# IV9.net
KiCad netlist of a schematic drawn in EAGLE
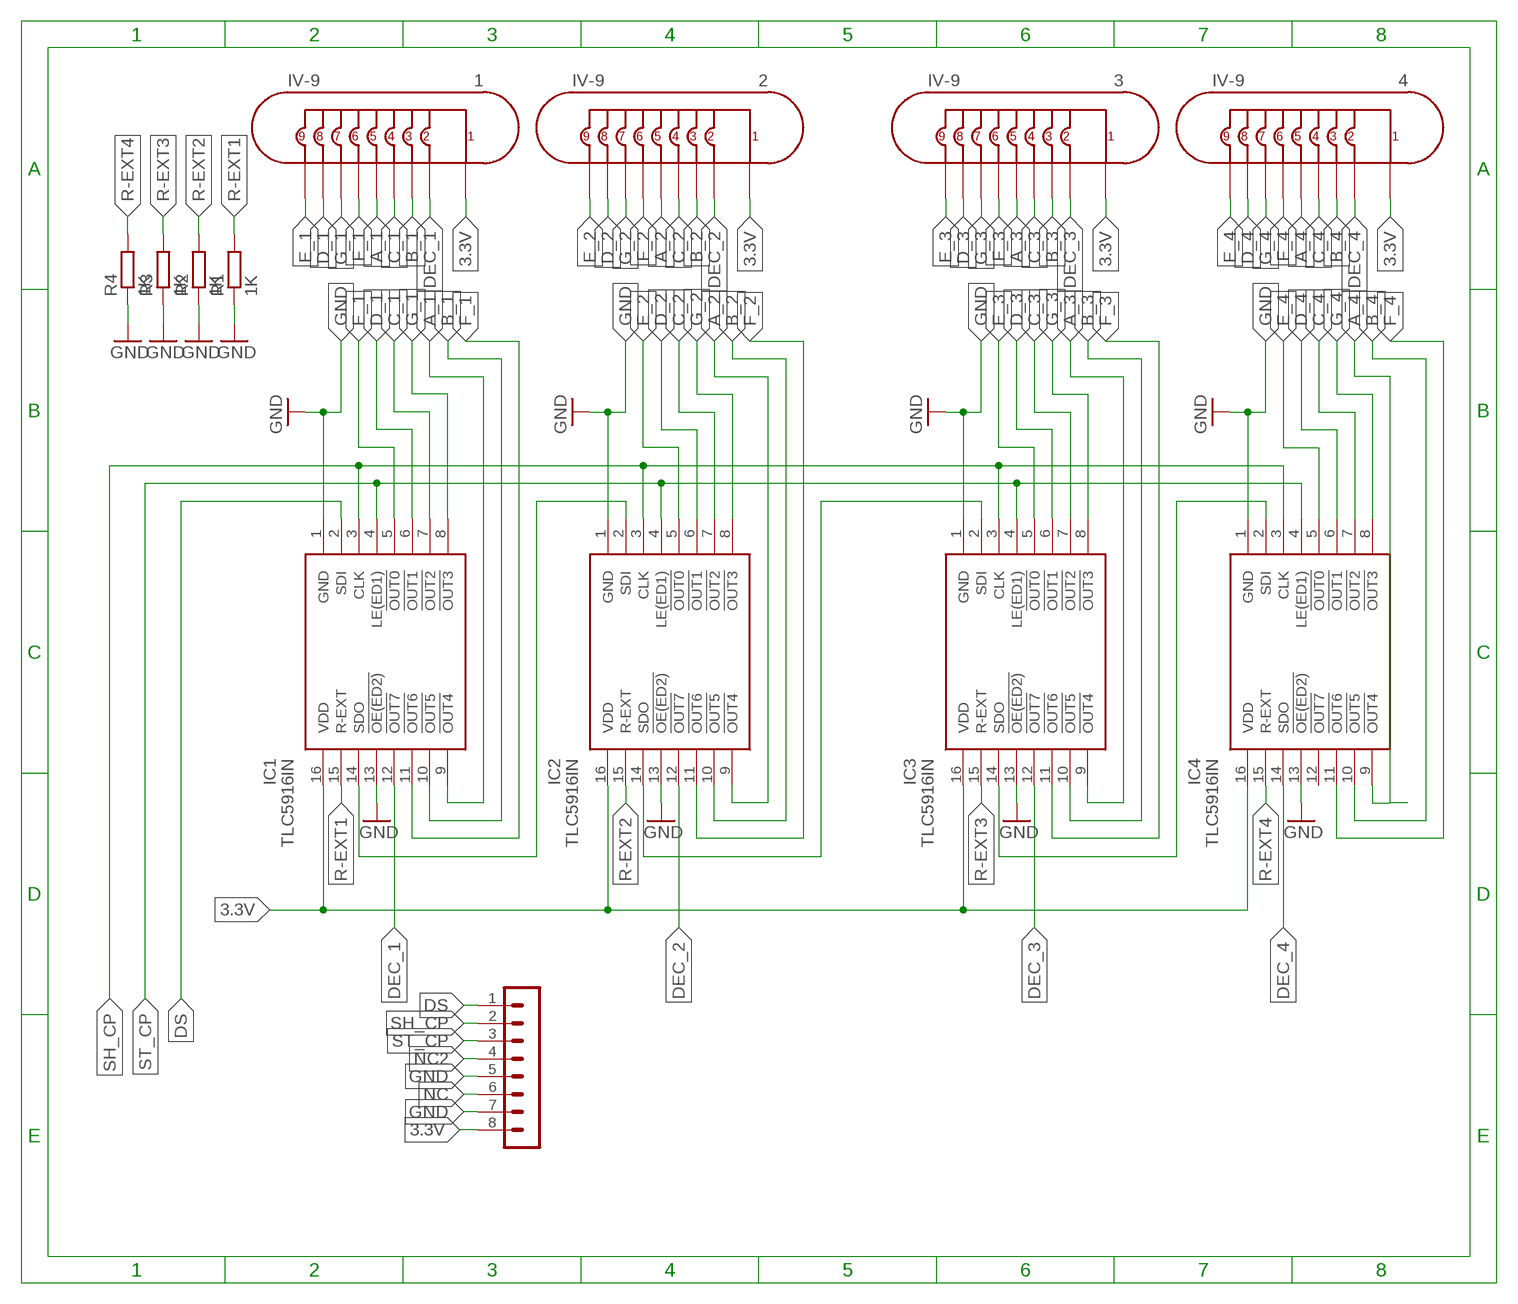
[diagram p0: schematic, sheet 1]

(export (version "E")
  (design (tool "Eeschema 10.0.6"))
  (components
    (comp (ref "1")
      (value "IV-9")
      (footprint "eagle-import:IV-9")
      (libsource (lib "eagle-import") (part "IV-9"))
    )
    (comp (ref "2")
      (value "IV-9")
      (footprint "eagle-import:IV-9")
      (libsource (lib "eagle-import") (part "IV-9"))
    )
    (comp (ref "3")
      (value "IV-9")
      (footprint "eagle-import:IV-9")
      (libsource (lib "eagle-import") (part "IV-9"))
    )
    (comp (ref "4")
      (value "IV-9")
      (footprint "eagle-import:IV-9")
      (libsource (lib "eagle-import") (part "IV-9"))
    )
    (comp (ref "IC1")
      (value "TLC5916IN")
      (footprint "eagle-import:DIP794W53P254L1930H508Q16N")
      (fields (field (name "MOUSER_PART_NUMBER") "595-TLC5916IN"))
      (libsource (lib "eagle-import") (part "TLC5916IN"))
    )
    (comp (ref "IC2")
      (value "TLC5916IN")
      (footprint "eagle-import:DIP794W53P254L1930H508Q16N")
      (fields (field (name "MOUSER_PART_NUMBER") "595-TLC5916IN"))
      (libsource (lib "eagle-import") (part "TLC5916IN"))
    )
    (comp (ref "IC3")
      (value "TLC5916IN")
      (footprint "eagle-import:DIP794W53P254L1930H508Q16N")
      (fields (field (name "MOUSER_PART_NUMBER") "595-TLC5916IN"))
      (libsource (lib "eagle-import") (part "TLC5916IN"))
    )
    (comp (ref "IC4")
      (value "TLC5916IN")
      (footprint "eagle-import:DIP794W53P254L1930H508Q16N")
      (fields (field (name "MOUSER_PART_NUMBER") "595-TLC5916IN"))
      (libsource (lib "eagle-import") (part "TLC5916IN"))
    )
    (comp (ref "R1")
      (value "1K")
      (footprint "eagle-import:R1206")
      (libsource (lib "eagle-import") (part "R-EU_R1206"))
    )
    (comp (ref "R2")
      (value "1K")
      (footprint "eagle-import:R1206")
      (libsource (lib "eagle-import") (part "R-EU_R1206"))
    )
    (comp (ref "R3")
      (value "1K")
      (footprint "eagle-import:R1206")
      (libsource (lib "eagle-import") (part "R-EU_R1206"))
    )
    (comp (ref "R4")
      (value "1K")
      (footprint "eagle-import:R1206")
      (libsource (lib "eagle-import") (part "R-EU_R1206"))
    )
    (comp (ref "SV2")
      (value "PINHEADER-1X8")
      (footprint "eagle-import:MA08-1")
      (libsource (lib "eagle-import") (part "PINHEADER-1X8"))
    )
  )
  (nets
    (net (code "1") (name "3.3V") (class "Default")
      (node (ref "1") (pin "1") (pinfunction "1_1") (pintype "bidirectional"))
      (node (ref "2") (pin "1") (pinfunction "1_1") (pintype "bidirectional"))
      (node (ref "3") (pin "1") (pinfunction "1_1") (pintype "bidirectional"))
      (node (ref "4") (pin "1") (pinfunction "1_1") (pintype "bidirectional"))
      (node (ref "IC1") (pin "16") (pinfunction "VDD_16") (pintype "bidirectional"))
      (node (ref "IC2") (pin "16") (pinfunction "VDD_16") (pintype "bidirectional"))
      (node (ref "IC3") (pin "16") (pinfunction "VDD_16") (pintype "bidirectional"))
      (node (ref "IC4") (pin "16") (pinfunction "VDD_16") (pintype "bidirectional"))
      (node (ref "SV2") (pin "8") (pinfunction "8_8") (pintype "passive"))
    )
    (net (code "2") (name "A_1") (class "Default")
      (node (ref "1") (pin "5") (pinfunction "5_5") (pintype "bidirectional"))
      (node (ref "IC1") (pin "9") (pinfunction "~{OUT4}_9") (pintype "bidirectional"))
    )
    (net (code "3") (name "A_2") (class "Default")
      (node (ref "2") (pin "5") (pinfunction "5_5") (pintype "bidirectional"))
      (node (ref "IC2") (pin "9") (pinfunction "~{OUT4}_9") (pintype "bidirectional"))
    )
    (net (code "4") (name "A_3") (class "Default")
      (node (ref "3") (pin "5") (pinfunction "5_5") (pintype "bidirectional"))
      (node (ref "IC3") (pin "9") (pinfunction "~{OUT4}_9") (pintype "bidirectional"))
    )
    (net (code "5") (name "A_4") (class "Default")
      (node (ref "4") (pin "5") (pinfunction "5_5") (pintype "bidirectional"))
      (node (ref "IC4") (pin "9") (pinfunction "~{OUT4}_9") (pintype "bidirectional"))
    )
    (net (code "6") (name "B_1") (class "Default")
      (node (ref "1") (pin "3") (pinfunction "3_3") (pintype "bidirectional"))
      (node (ref "IC1") (pin "10") (pinfunction "~{OUT5}_10") (pintype "bidirectional"))
    )
    (net (code "7") (name "B_2") (class "Default")
      (node (ref "2") (pin "3") (pinfunction "3_3") (pintype "bidirectional"))
      (node (ref "IC2") (pin "10") (pinfunction "~{OUT5}_10") (pintype "bidirectional"))
    )
    (net (code "8") (name "B_3") (class "Default")
      (node (ref "3") (pin "3") (pinfunction "3_3") (pintype "bidirectional"))
      (node (ref "IC3") (pin "10") (pinfunction "~{OUT5}_10") (pintype "bidirectional"))
    )
    (net (code "9") (name "B_4") (class "Default")
      (node (ref "4") (pin "3") (pinfunction "3_3") (pintype "bidirectional"))
      (node (ref "IC4") (pin "10") (pinfunction "~{OUT5}_10") (pintype "bidirectional"))
    )
    (net (code "10") (name "C_1") (class "Default")
      (node (ref "1") (pin "4") (pinfunction "4_4") (pintype "bidirectional"))
      (node (ref "IC1") (pin "7") (pinfunction "~{OUT2}_7") (pintype "bidirectional"))
    )
    (net (code "11") (name "C_2") (class "Default")
      (node (ref "2") (pin "4") (pinfunction "4_4") (pintype "bidirectional"))
      (node (ref "IC2") (pin "7") (pinfunction "~{OUT2}_7") (pintype "bidirectional"))
    )
    (net (code "12") (name "C_3") (class "Default")
      (node (ref "3") (pin "4") (pinfunction "4_4") (pintype "bidirectional"))
      (node (ref "IC3") (pin "7") (pinfunction "~{OUT2}_7") (pintype "bidirectional"))
    )
    (net (code "13") (name "C_4") (class "Default")
      (node (ref "4") (pin "4") (pinfunction "4_4") (pintype "bidirectional"))
      (node (ref "IC4") (pin "7") (pinfunction "~{OUT2}_7") (pintype "bidirectional"))
    )
    (net (code "14") (name "DEC_1") (class "Default")
      (node (ref "1") (pin "2") (pinfunction "2_2") (pintype "bidirectional"))
      (node (ref "IC1") (pin "12") (pinfunction "~{OUT7}_12") (pintype "bidirectional"))
    )
    (net (code "15") (name "DEC_2") (class "Default")
      (node (ref "2") (pin "2") (pinfunction "2_2") (pintype "bidirectional"))
      (node (ref "IC2") (pin "12") (pinfunction "~{OUT7}_12") (pintype "bidirectional"))
    )
    (net (code "16") (name "DEC_3") (class "Default")
      (node (ref "3") (pin "2") (pinfunction "2_2") (pintype "bidirectional"))
      (node (ref "IC3") (pin "12") (pinfunction "~{OUT7}_12") (pintype "bidirectional"))
    )
    (net (code "17") (name "DEC_4") (class "Default")
      (node (ref "4") (pin "2") (pinfunction "2_2") (pintype "bidirectional"))
      (node (ref "IC4") (pin "14") (pinfunction "SDO_14") (pintype "bidirectional"))
    )
    (net (code "18") (name "DS") (class "Default")
      (node (ref "IC1") (pin "2") (pinfunction "SDI_2") (pintype "bidirectional"))
      (node (ref "SV2") (pin "1") (pinfunction "1_1") (pintype "passive"))
    )
    (net (code "19") (name "D_1") (class "Default")
      (node (ref "1") (pin "8") (pinfunction "8_8") (pintype "bidirectional"))
      (node (ref "IC1") (pin "6") (pinfunction "~{OUT1}_6") (pintype "bidirectional"))
    )
    (net (code "20") (name "D_2") (class "Default")
      (node (ref "2") (pin "8") (pinfunction "8_8") (pintype "bidirectional"))
      (node (ref "IC2") (pin "6") (pinfunction "~{OUT1}_6") (pintype "bidirectional"))
    )
    (net (code "21") (name "D_3") (class "Default")
      (node (ref "3") (pin "8") (pinfunction "8_8") (pintype "bidirectional"))
      (node (ref "IC3") (pin "6") (pinfunction "~{OUT1}_6") (pintype "bidirectional"))
    )
    (net (code "22") (name "D_4") (class "Default")
      (node (ref "4") (pin "8") (pinfunction "8_8") (pintype "bidirectional"))
      (node (ref "IC4") (pin "6") (pinfunction "~{OUT1}_6") (pintype "bidirectional"))
    )
    (net (code "23") (name "E_1") (class "Default")
      (node (ref "1") (pin "9") (pinfunction "9_9") (pintype "bidirectional"))
      (node (ref "IC1") (pin "5") (pinfunction "~{OUT0}_5") (pintype "bidirectional"))
    )
    (net (code "24") (name "E_2") (class "Default")
      (node (ref "2") (pin "9") (pinfunction "9_9") (pintype "bidirectional"))
      (node (ref "IC2") (pin "5") (pinfunction "~{OUT0}_5") (pintype "bidirectional"))
    )
    (net (code "25") (name "E_3") (class "Default")
      (node (ref "3") (pin "9") (pinfunction "9_9") (pintype "bidirectional"))
      (node (ref "IC3") (pin "5") (pinfunction "~{OUT0}_5") (pintype "bidirectional"))
    )
    (net (code "26") (name "E_4") (class "Default")
      (node (ref "4") (pin "9") (pinfunction "9_9") (pintype "bidirectional"))
      (node (ref "IC4") (pin "5") (pinfunction "~{OUT0}_5") (pintype "bidirectional"))
    )
    (net (code "27") (name "F_1") (class "Default")
      (node (ref "1") (pin "6") (pinfunction "6_6") (pintype "bidirectional"))
      (node (ref "IC1") (pin "11") (pinfunction "~{OUT6}_11") (pintype "bidirectional"))
    )
    (net (code "28") (name "F_2") (class "Default")
      (node (ref "2") (pin "6") (pinfunction "6_6") (pintype "bidirectional"))
      (node (ref "IC2") (pin "11") (pinfunction "~{OUT6}_11") (pintype "bidirectional"))
    )
    (net (code "29") (name "F_3") (class "Default")
      (node (ref "3") (pin "6") (pinfunction "6_6") (pintype "bidirectional"))
      (node (ref "IC3") (pin "11") (pinfunction "~{OUT6}_11") (pintype "bidirectional"))
    )
    (net (code "30") (name "F_4") (class "Default")
      (node (ref "4") (pin "6") (pinfunction "6_6") (pintype "bidirectional"))
      (node (ref "IC4") (pin "11") (pinfunction "~{OUT6}_11") (pintype "bidirectional"))
    )
    (net (code "31") (name "GND") (class "Default")
      (node (ref "IC1") (pin "1") (pinfunction "GND_1") (pintype "bidirectional"))
      (node (ref "IC1") (pin "13") (pinfunction "~{OE(ED2})_13") (pintype "bidirectional"))
      (node (ref "IC2") (pin "1") (pinfunction "GND_1") (pintype "bidirectional"))
      (node (ref "IC2") (pin "13") (pinfunction "~{OE(ED2})_13") (pintype "bidirectional"))
      (node (ref "IC3") (pin "1") (pinfunction "GND_1") (pintype "bidirectional"))
      (node (ref "IC3") (pin "13") (pinfunction "~{OE(ED2})_13") (pintype "bidirectional"))
      (node (ref "IC4") (pin "1") (pinfunction "GND_1") (pintype "bidirectional"))
      (node (ref "IC4") (pin "13") (pinfunction "~{OE(ED2})_13") (pintype "bidirectional"))
      (node (ref "R1") (pin "1") (pinfunction "1_1") (pintype "passive"))
      (node (ref "R2") (pin "1") (pinfunction "1_1") (pintype "passive"))
      (node (ref "R3") (pin "1") (pinfunction "1_1") (pintype "passive"))
      (node (ref "R4") (pin "1") (pinfunction "1_1") (pintype "passive"))
      (node (ref "SV2") (pin "5") (pinfunction "5_5") (pintype "passive"))
      (node (ref "SV2") (pin "7") (pinfunction "7_7") (pintype "passive"))
    )
    (net (code "32") (name "G_1") (class "Default")
      (node (ref "1") (pin "7") (pinfunction "7_7") (pintype "bidirectional"))
      (node (ref "IC1") (pin "8") (pinfunction "~{OUT3}_8") (pintype "bidirectional"))
    )
    (net (code "33") (name "G_2") (class "Default")
      (node (ref "2") (pin "7") (pinfunction "7_7") (pintype "bidirectional"))
      (node (ref "IC2") (pin "8") (pinfunction "~{OUT3}_8") (pintype "bidirectional"))
    )
    (net (code "34") (name "G_3") (class "Default")
      (node (ref "3") (pin "7") (pinfunction "7_7") (pintype "bidirectional"))
      (node (ref "IC3") (pin "8") (pinfunction "~{OUT3}_8") (pintype "bidirectional"))
    )
    (net (code "35") (name "G_4") (class "Default")
      (node (ref "4") (pin "7") (pinfunction "7_7") (pintype "bidirectional"))
      (node (ref "IC4") (pin "8") (pinfunction "~{OUT3}_8") (pintype "bidirectional"))
    )
    (net (code "36") (name "NC") (class "Default")
      (node (ref "SV2") (pin "6") (pinfunction "6_6") (pintype "passive"))
    )
    (net (code "37") (name "NC2") (class "Default")
      (node (ref "SV2") (pin "4") (pinfunction "4_4") (pintype "passive"))
    )
    (net (code "38") (name "Net-(IC1-SDO)") (class "Default")
      (node (ref "IC1") (pin "14") (pinfunction "SDO_14") (pintype "bidirectional"))
      (node (ref "IC2") (pin "2") (pinfunction "SDI_2") (pintype "bidirectional"))
    )
    (net (code "39") (name "Net-(IC2-SDO)") (class "Default")
      (node (ref "IC2") (pin "14") (pinfunction "SDO_14") (pintype "bidirectional"))
      (node (ref "IC3") (pin "2") (pinfunction "SDI_2") (pintype "bidirectional"))
    )
    (net (code "40") (name "Net-(IC3-SDO)") (class "Default")
      (node (ref "IC3") (pin "14") (pinfunction "SDO_14") (pintype "bidirectional"))
      (node (ref "IC4") (pin "2") (pinfunction "SDI_2") (pintype "bidirectional"))
    )
    (net (code "41") (name "R-EXT1") (class "Default")
      (node (ref "IC1") (pin "15") (pinfunction "R-EXT_15") (pintype "bidirectional"))
      (node (ref "R1") (pin "2") (pinfunction "2_2") (pintype "passive"))
    )
    (net (code "42") (name "R-EXT2") (class "Default")
      (node (ref "IC2") (pin "15") (pinfunction "R-EXT_15") (pintype "bidirectional"))
      (node (ref "R2") (pin "2") (pinfunction "2_2") (pintype "passive"))
    )
    (net (code "43") (name "R-EXT3") (class "Default")
      (node (ref "IC3") (pin "15") (pinfunction "R-EXT_15") (pintype "bidirectional"))
      (node (ref "R3") (pin "2") (pinfunction "2_2") (pintype "passive"))
    )
    (net (code "44") (name "R-EXT4") (class "Default")
      (node (ref "IC4") (pin "15") (pinfunction "R-EXT_15") (pintype "bidirectional"))
      (node (ref "R4") (pin "2") (pinfunction "2_2") (pintype "passive"))
    )
    (net (code "45") (name "SH_CP") (class "Default")
      (node (ref "IC1") (pin "3") (pinfunction "CLK_3") (pintype "bidirectional"))
      (node (ref "IC2") (pin "3") (pinfunction "CLK_3") (pintype "bidirectional"))
      (node (ref "IC3") (pin "3") (pinfunction "CLK_3") (pintype "bidirectional"))
      (node (ref "IC4") (pin "3") (pinfunction "CLK_3") (pintype "bidirectional"))
      (node (ref "SV2") (pin "2") (pinfunction "2_2") (pintype "passive"))
    )
    (net (code "46") (name "ST_CP") (class "Default")
      (node (ref "IC1") (pin "4") (pinfunction "LE(ED1)_4") (pintype "bidirectional"))
      (node (ref "IC2") (pin "4") (pinfunction "LE(ED1)_4") (pintype "bidirectional"))
      (node (ref "IC3") (pin "4") (pinfunction "LE(ED1)_4") (pintype "bidirectional"))
      (node (ref "IC4") (pin "4") (pinfunction "LE(ED1)_4") (pintype "bidirectional"))
      (node (ref "SV2") (pin "3") (pinfunction "3_3") (pintype "passive"))
    )
    (net (code "47") (name "unconnected-(IC4-~{OUT7}-Pad12)") (class "Default")
      (node (ref "IC4") (pin "12") (pinfunction "~{OUT7}_12") (pintype "bidirectional"))
    )
  )
)
